# R220J.net
KiCad netlist of a schematic drawn in EAGLE
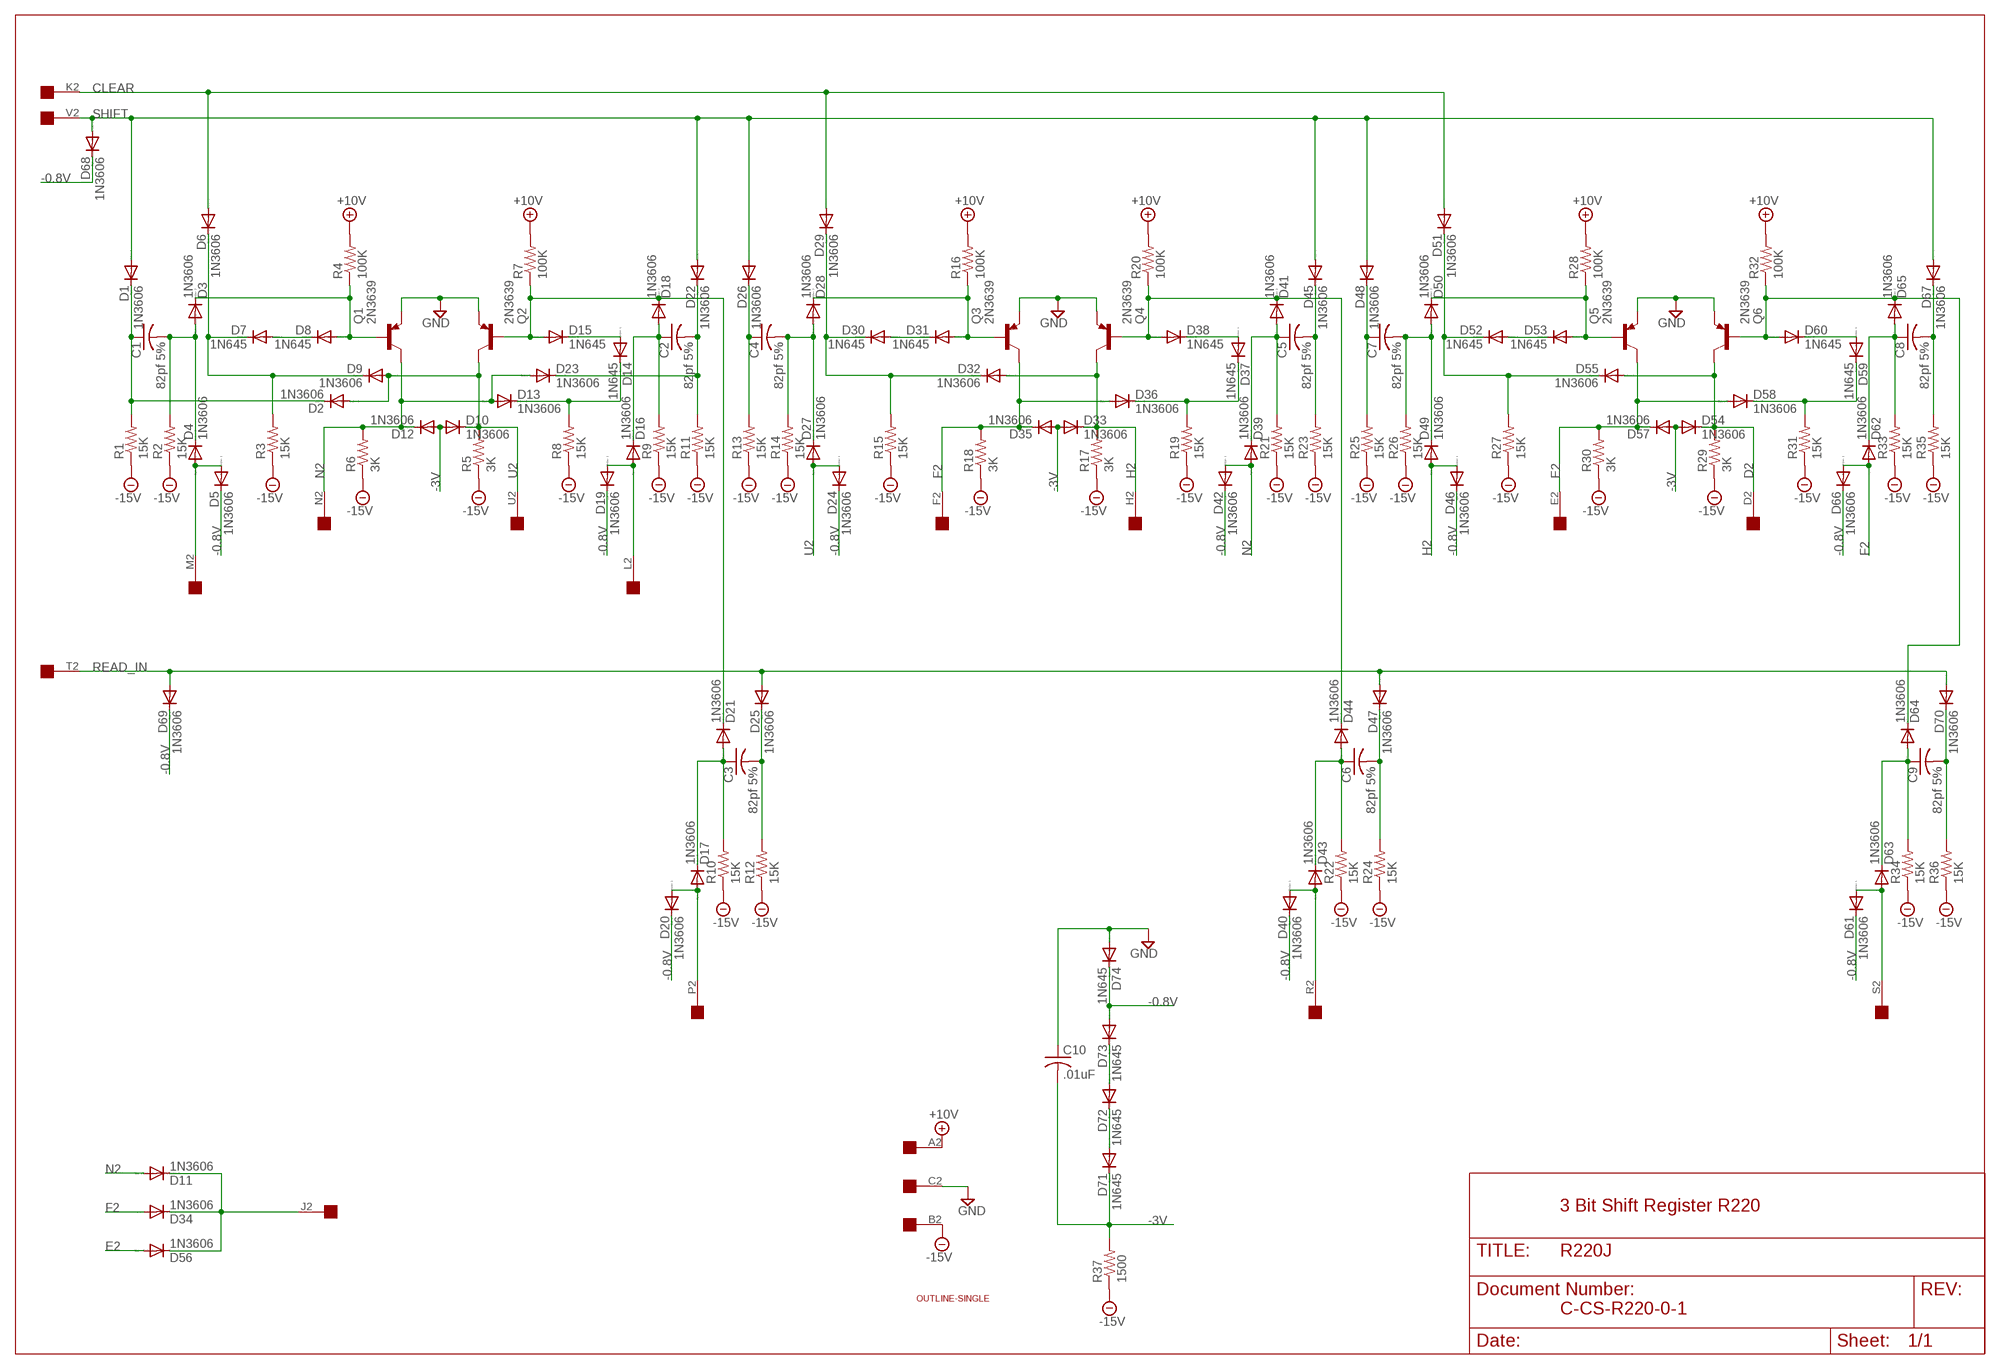
[diagram p0: schematic, sheet 1]

(export (version "E")
  (design (tool "Eeschema 10.0.6"))
  (components
    (comp (ref "C1")
      (value "82pf 5%")
      (footprint "eagle-import:C050-025X075")
      (libsource (lib "eagle-import") (part "C-US050-025X075"))
    )
    (comp (ref "C2")
      (value "82pf 5%")
      (footprint "eagle-import:C050-025X075")
      (libsource (lib "eagle-import") (part "C-US050-025X075"))
    )
    (comp (ref "C3")
      (value "82pf 5%")
      (footprint "eagle-import:C050-025X075")
      (libsource (lib "eagle-import") (part "C-US050-025X075"))
    )
    (comp (ref "C4")
      (value "82pf 5%")
      (footprint "eagle-import:C050-025X075")
      (libsource (lib "eagle-import") (part "C-US050-025X075"))
    )
    (comp (ref "C5")
      (value "82pf 5%")
      (footprint "eagle-import:C050-025X075")
      (libsource (lib "eagle-import") (part "C-US050-025X075"))
    )
    (comp (ref "C6")
      (value "82pf 5%")
      (footprint "eagle-import:C050-025X075")
      (libsource (lib "eagle-import") (part "C-US050-025X075"))
    )
    (comp (ref "C7")
      (value "82pf 5%")
      (footprint "eagle-import:C050-025X075")
      (libsource (lib "eagle-import") (part "C-US050-025X075"))
    )
    (comp (ref "C8")
      (value "82pf 5%")
      (footprint "eagle-import:C050-025X075")
      (libsource (lib "eagle-import") (part "C-US050-025X075"))
    )
    (comp (ref "C9")
      (value "82pf 5%")
      (footprint "eagle-import:C050-025X075")
      (libsource (lib "eagle-import") (part "C-US050-025X075"))
    )
    (comp (ref "C10")
      (value ".01uF")
      (footprint "eagle-import:C050-025X075")
      (libsource (lib "eagle-import") (part "C-US050-025X075"))
    )
    (comp (ref "D1")
      (value "1N3606")
      (footprint "eagle-import:DO35-10")
      (libsource (lib "eagle-import") (part "1N4148DO35-10"))
    )
    (comp (ref "D2")
      (value "1N3606")
      (footprint "eagle-import:DO35-10")
      (libsource (lib "eagle-import") (part "1N4148DO35-10"))
    )
    (comp (ref "D3")
      (value "1N3606")
      (footprint "eagle-import:DO35-10")
      (libsource (lib "eagle-import") (part "1N4148DO35-10"))
    )
    (comp (ref "D4")
      (value "1N3606")
      (footprint "eagle-import:DO35-10")
      (libsource (lib "eagle-import") (part "1N4148DO35-10"))
    )
    (comp (ref "D5")
      (value "1N3606")
      (footprint "eagle-import:DO35-10")
      (libsource (lib "eagle-import") (part "1N4148DO35-10"))
    )
    (comp (ref "D6")
      (value "1N3606")
      (footprint "eagle-import:DO35-10")
      (libsource (lib "eagle-import") (part "1N4148DO35-10"))
    )
    (comp (ref "D7")
      (value "1N645")
      (footprint "eagle-import:DO35-10")
      (libsource (lib "eagle-import") (part "1N4148DO35-10"))
    )
    (comp (ref "D8")
      (value "1N645")
      (footprint "eagle-import:DO35-10")
      (libsource (lib "eagle-import") (part "1N4148DO35-10"))
    )
    (comp (ref "D9")
      (value "1N3606")
      (footprint "eagle-import:DO35-10")
      (libsource (lib "eagle-import") (part "1N4148DO35-10"))
    )
    (comp (ref "D10")
      (value "1N3606")
      (footprint "eagle-import:DO35-10")
      (libsource (lib "eagle-import") (part "1N4148DO35-10"))
    )
    (comp (ref "D11")
      (value "1N3606")
      (footprint "eagle-import:DO35-10")
      (libsource (lib "eagle-import") (part "1N4148DO35-10"))
    )
    (comp (ref "D12")
      (value "1N3606")
      (footprint "eagle-import:DO35-10")
      (libsource (lib "eagle-import") (part "1N4148DO35-10"))
    )
    (comp (ref "D13")
      (value "1N3606")
      (footprint "eagle-import:DO35-10")
      (libsource (lib "eagle-import") (part "1N4148DO35-10"))
    )
    (comp (ref "D14")
      (value "1N645")
      (footprint "eagle-import:DO35-10")
      (libsource (lib "eagle-import") (part "1N4148DO35-10"))
    )
    (comp (ref "D15")
      (value "1N645")
      (footprint "eagle-import:DO35-10")
      (libsource (lib "eagle-import") (part "1N4148DO35-10"))
    )
    (comp (ref "D16")
      (value "1N3606")
      (footprint "eagle-import:DO35-10")
      (libsource (lib "eagle-import") (part "1N4148DO35-10"))
    )
    (comp (ref "D17")
      (value "1N3606")
      (footprint "eagle-import:DO35-10")
      (libsource (lib "eagle-import") (part "1N4148DO35-10"))
    )
    (comp (ref "D18")
      (value "1N3606")
      (footprint "eagle-import:DO35-10")
      (libsource (lib "eagle-import") (part "1N4148DO35-10"))
    )
    (comp (ref "D19")
      (value "1N3606")
      (footprint "eagle-import:DO35-10")
      (libsource (lib "eagle-import") (part "1N4148DO35-10"))
    )
    (comp (ref "D20")
      (value "1N3606")
      (footprint "eagle-import:DO35-10")
      (libsource (lib "eagle-import") (part "1N4148DO35-10"))
    )
    (comp (ref "D21")
      (value "1N3606")
      (footprint "eagle-import:DO35-10")
      (libsource (lib "eagle-import") (part "1N4148DO35-10"))
    )
    (comp (ref "D22")
      (value "1N3606")
      (footprint "eagle-import:DO35-10")
      (libsource (lib "eagle-import") (part "1N4148DO35-10"))
    )
    (comp (ref "D23")
      (value "1N3606")
      (footprint "eagle-import:DO35-10")
      (libsource (lib "eagle-import") (part "1N4148DO35-10"))
    )
    (comp (ref "D24")
      (value "1N3606")
      (footprint "eagle-import:DO35-10")
      (libsource (lib "eagle-import") (part "1N4148DO35-10"))
    )
    (comp (ref "D25")
      (value "1N3606")
      (footprint "eagle-import:DO35-10")
      (libsource (lib "eagle-import") (part "1N4148DO35-10"))
    )
    (comp (ref "D26")
      (value "1N3606")
      (footprint "eagle-import:DO35-10")
      (libsource (lib "eagle-import") (part "1N4148DO35-10"))
    )
    (comp (ref "D27")
      (value "1N3606")
      (footprint "eagle-import:DO35-10")
      (libsource (lib "eagle-import") (part "1N4148DO35-10"))
    )
    (comp (ref "D28")
      (value "1N3606")
      (footprint "eagle-import:DO35-10")
      (libsource (lib "eagle-import") (part "1N4148DO35-10"))
    )
    (comp (ref "D29")
      (value "1N3606")
      (footprint "eagle-import:DO35-10")
      (libsource (lib "eagle-import") (part "1N4148DO35-10"))
    )
    (comp (ref "D30")
      (value "1N645")
      (footprint "eagle-import:DO35-10")
      (libsource (lib "eagle-import") (part "1N4148DO35-10"))
    )
    (comp (ref "D31")
      (value "1N645")
      (footprint "eagle-import:DO35-10")
      (libsource (lib "eagle-import") (part "1N4148DO35-10"))
    )
    (comp (ref "D32")
      (value "1N3606")
      (footprint "eagle-import:DO35-10")
      (libsource (lib "eagle-import") (part "1N4148DO35-10"))
    )
    (comp (ref "D33")
      (value "1N3606")
      (footprint "eagle-import:DO35-10")
      (libsource (lib "eagle-import") (part "1N4148DO35-10"))
    )
    (comp (ref "D34")
      (value "1N3606")
      (footprint "eagle-import:DO35-10")
      (libsource (lib "eagle-import") (part "1N4148DO35-10"))
    )
    (comp (ref "D35")
      (value "1N3606")
      (footprint "eagle-import:DO35-10")
      (libsource (lib "eagle-import") (part "1N4148DO35-10"))
    )
    (comp (ref "D36")
      (value "1N3606")
      (footprint "eagle-import:DO35-10")
      (libsource (lib "eagle-import") (part "1N4148DO35-10"))
    )
    (comp (ref "D37")
      (value "1N645")
      (footprint "eagle-import:DO35-10")
      (libsource (lib "eagle-import") (part "1N4148DO35-10"))
    )
    (comp (ref "D38")
      (value "1N645")
      (footprint "eagle-import:DO35-10")
      (libsource (lib "eagle-import") (part "1N4148DO35-10"))
    )
    (comp (ref "D39")
      (value "1N3606")
      (footprint "eagle-import:DO35-10")
      (libsource (lib "eagle-import") (part "1N4148DO35-10"))
    )
    (comp (ref "D40")
      (value "1N3606")
      (footprint "eagle-import:DO35-10")
      (libsource (lib "eagle-import") (part "1N4148DO35-10"))
    )
    (comp (ref "D41")
      (value "1N3606")
      (footprint "eagle-import:DO35-10")
      (libsource (lib "eagle-import") (part "1N4148DO35-10"))
    )
    (comp (ref "D42")
      (value "1N3606")
      (footprint "eagle-import:DO35-10")
      (libsource (lib "eagle-import") (part "1N4148DO35-10"))
    )
    (comp (ref "D43")
      (value "1N3606")
      (footprint "eagle-import:DO35-10")
      (libsource (lib "eagle-import") (part "1N4148DO35-10"))
    )
    (comp (ref "D44")
      (value "1N3606")
      (footprint "eagle-import:DO35-10")
      (libsource (lib "eagle-import") (part "1N4148DO35-10"))
    )
    (comp (ref "D45")
      (value "1N3606")
      (footprint "eagle-import:DO35-10")
      (libsource (lib "eagle-import") (part "1N4148DO35-10"))
    )
    (comp (ref "D46")
      (value "1N3606")
      (footprint "eagle-import:DO35-10")
      (libsource (lib "eagle-import") (part "1N4148DO35-10"))
    )
    (comp (ref "D47")
      (value "1N3606")
      (footprint "eagle-import:DO35-10")
      (libsource (lib "eagle-import") (part "1N4148DO35-10"))
    )
    (comp (ref "D48")
      (value "1N3606")
      (footprint "eagle-import:DO35-10")
      (libsource (lib "eagle-import") (part "1N4148DO35-10"))
    )
    (comp (ref "D49")
      (value "1N3606")
      (footprint "eagle-import:DO35-10")
      (libsource (lib "eagle-import") (part "1N4148DO35-10"))
    )
    (comp (ref "D50")
      (value "1N3606")
      (footprint "eagle-import:DO35-10")
      (libsource (lib "eagle-import") (part "1N4148DO35-10"))
    )
    (comp (ref "D51")
      (value "1N3606")
      (footprint "eagle-import:DO35-10")
      (libsource (lib "eagle-import") (part "1N4148DO35-10"))
    )
    (comp (ref "D52")
      (value "1N645")
      (footprint "eagle-import:DO35-10")
      (libsource (lib "eagle-import") (part "1N4148DO35-10"))
    )
    (comp (ref "D53")
      (value "1N645")
      (footprint "eagle-import:DO35-10")
      (libsource (lib "eagle-import") (part "1N4148DO35-10"))
    )
    (comp (ref "D54")
      (value "1N3606")
      (footprint "eagle-import:DO35-10")
      (libsource (lib "eagle-import") (part "1N4148DO35-10"))
    )
    (comp (ref "D55")
      (value "1N3606")
      (footprint "eagle-import:DO35-10")
      (libsource (lib "eagle-import") (part "1N4148DO35-10"))
    )
    (comp (ref "D56")
      (value "1N3606")
      (footprint "eagle-import:DO35-10")
      (libsource (lib "eagle-import") (part "1N4148DO35-10"))
    )
    (comp (ref "D57")
      (value "1N3606")
      (footprint "eagle-import:DO35-10")
      (libsource (lib "eagle-import") (part "1N4148DO35-10"))
    )
    (comp (ref "D58")
      (value "1N3606")
      (footprint "eagle-import:DO35-10")
      (libsource (lib "eagle-import") (part "1N4148DO35-10"))
    )
    (comp (ref "D59")
      (value "1N645")
      (footprint "eagle-import:DO35-10")
      (libsource (lib "eagle-import") (part "1N4148DO35-10"))
    )
    (comp (ref "D60")
      (value "1N645")
      (footprint "eagle-import:DO35-10")
      (libsource (lib "eagle-import") (part "1N4148DO35-10"))
    )
    (comp (ref "D61")
      (value "1N3606")
      (footprint "eagle-import:DO35-10")
      (libsource (lib "eagle-import") (part "1N4148DO35-10"))
    )
    (comp (ref "D62")
      (value "1N3606")
      (footprint "eagle-import:DO35-10")
      (libsource (lib "eagle-import") (part "1N4148DO35-10"))
    )
    (comp (ref "D63")
      (value "1N3606")
      (footprint "eagle-import:DO35-10")
      (libsource (lib "eagle-import") (part "1N4148DO35-10"))
    )
    (comp (ref "D64")
      (value "1N3606")
      (footprint "eagle-import:DO35-10")
      (libsource (lib "eagle-import") (part "1N4148DO35-10"))
    )
    (comp (ref "D65")
      (value "1N3606")
      (footprint "eagle-import:DO35-10")
      (libsource (lib "eagle-import") (part "1N4148DO35-10"))
    )
    (comp (ref "D66")
      (value "1N3606")
      (footprint "eagle-import:DO35-10")
      (libsource (lib "eagle-import") (part "1N4148DO35-10"))
    )
    (comp (ref "D67")
      (value "1N3606")
      (footprint "eagle-import:DO35-10")
      (libsource (lib "eagle-import") (part "1N4148DO35-10"))
    )
    (comp (ref "D68")
      (value "1N3606")
      (footprint "eagle-import:DO35-10")
      (libsource (lib "eagle-import") (part "1N4148DO35-10"))
    )
    (comp (ref "D69")
      (value "1N3606")
      (footprint "eagle-import:DO35-10")
      (libsource (lib "eagle-import") (part "1N4148DO35-10"))
    )
    (comp (ref "D70")
      (value "1N3606")
      (footprint "eagle-import:DO35-10")
      (libsource (lib "eagle-import") (part "1N4148DO35-10"))
    )
    (comp (ref "D71")
      (value "1N645")
      (footprint "eagle-import:DO35-10")
      (libsource (lib "eagle-import") (part "1N4148DO35-10"))
    )
    (comp (ref "D72")
      (value "1N645")
      (footprint "eagle-import:DO35-10")
      (libsource (lib "eagle-import") (part "1N4148DO35-10"))
    )
    (comp (ref "D73")
      (value "1N645")
      (footprint "eagle-import:DO35-10")
      (libsource (lib "eagle-import") (part "1N4148DO35-10"))
    )
    (comp (ref "D74")
      (value "1N645")
      (footprint "eagle-import:DO35-10")
      (libsource (lib "eagle-import") (part "1N4148DO35-10"))
    )
    (comp (ref "Q1")
      (value "2N3639")
      (footprint "eagle-import:TO39")
      (libsource (lib "eagle-import") (part "2N3637"))
    )
    (comp (ref "Q2")
      (value "2N3639")
      (footprint "eagle-import:TO39")
      (libsource (lib "eagle-import") (part "2N3637"))
    )
    (comp (ref "Q3")
      (value "2N3639")
      (footprint "eagle-import:TO39")
      (libsource (lib "eagle-import") (part "2N3637"))
    )
    (comp (ref "Q4")
      (value "2N3639")
      (footprint "eagle-import:TO39")
      (libsource (lib "eagle-import") (part "2N3637"))
    )
    (comp (ref "Q5")
      (value "2N3639")
      (footprint "eagle-import:TO39")
      (libsource (lib "eagle-import") (part "2N3637"))
    )
    (comp (ref "Q6")
      (value "2N3639")
      (footprint "eagle-import:TO39")
      (libsource (lib "eagle-import") (part "2N3637"))
    )
    (comp (ref "R1")
      (value "15K")
      (footprint "eagle-import:0207_10")
      (libsource (lib "eagle-import") (part "R-US_0207/10"))
    )
    (comp (ref "R2")
      (value "15K")
      (footprint "eagle-import:0207_10")
      (libsource (lib "eagle-import") (part "R-US_0207/10"))
    )
    (comp (ref "R3")
      (value "15K")
      (footprint "eagle-import:0207_10")
      (libsource (lib "eagle-import") (part "R-US_0207/10"))
    )
    (comp (ref "R4")
      (value "100K")
      (footprint "eagle-import:0207_10")
      (libsource (lib "eagle-import") (part "R-US_0207/10"))
    )
    (comp (ref "R5")
      (value "3K")
      (footprint "eagle-import:0207_10")
      (libsource (lib "eagle-import") (part "R-US_0207/10"))
    )
    (comp (ref "R6")
      (value "3K")
      (footprint "eagle-import:0207_10")
      (libsource (lib "eagle-import") (part "R-US_0207/10"))
    )
    (comp (ref "R7")
      (value "100K")
      (footprint "eagle-import:0207_10")
      (libsource (lib "eagle-import") (part "R-US_0207/10"))
    )
    (comp (ref "R8")
      (value "15K")
      (footprint "eagle-import:0207_10")
      (libsource (lib "eagle-import") (part "R-US_0207/10"))
    )
    (comp (ref "R9")
      (value "15K")
      (footprint "eagle-import:0207_10")
      (libsource (lib "eagle-import") (part "R-US_0207/10"))
    )
    (comp (ref "R10")
      (value "15K")
      (footprint "eagle-import:0207_10")
      (libsource (lib "eagle-import") (part "R-US_0207/10"))
    )
    (comp (ref "R11")
      (value "15K")
      (footprint "eagle-import:0207_10")
      (libsource (lib "eagle-import") (part "R-US_0207/10"))
    )
    (comp (ref "R12")
      (value "15K")
      (footprint "eagle-import:0207_10")
      (libsource (lib "eagle-import") (part "R-US_0207/10"))
    )
    (comp (ref "R13")
      (value "15K")
      (footprint "eagle-import:0207_10")
      (libsource (lib "eagle-import") (part "R-US_0207/10"))
    )
    (comp (ref "R14")
      (value "15K")
      (footprint "eagle-import:0207_10")
      (libsource (lib "eagle-import") (part "R-US_0207/10"))
    )
    (comp (ref "R15")
      (value "15K")
      (footprint "eagle-import:0207_10")
      (libsource (lib "eagle-import") (part "R-US_0207/10"))
    )
    (comp (ref "R16")
      (value "100K")
      (footprint "eagle-import:0207_10")
      (libsource (lib "eagle-import") (part "R-US_0207/10"))
    )
    (comp (ref "R17")
      (value "3K")
      (footprint "eagle-import:0207_10")
      (libsource (lib "eagle-import") (part "R-US_0207/10"))
    )
    (comp (ref "R18")
      (value "3K")
      (footprint "eagle-import:0207_10")
      (libsource (lib "eagle-import") (part "R-US_0207/10"))
    )
    (comp (ref "R19")
      (value "15K")
      (footprint "eagle-import:0207_10")
      (libsource (lib "eagle-import") (part "R-US_0207/10"))
    )
    (comp (ref "R20")
      (value "100K")
      (footprint "eagle-import:0207_10")
      (libsource (lib "eagle-import") (part "R-US_0207/10"))
    )
    (comp (ref "R21")
      (value "15K")
      (footprint "eagle-import:0207_10")
      (libsource (lib "eagle-import") (part "R-US_0207/10"))
    )
    (comp (ref "R22")
      (value "15K")
      (footprint "eagle-import:0207_10")
      (libsource (lib "eagle-import") (part "R-US_0207/10"))
    )
    (comp (ref "R23")
      (value "15K")
      (footprint "eagle-import:0207_10")
      (libsource (lib "eagle-import") (part "R-US_0207/10"))
    )
    (comp (ref "R24")
      (value "15K")
      (footprint "eagle-import:0207_10")
      (libsource (lib "eagle-import") (part "R-US_0207/10"))
    )
    (comp (ref "R25")
      (value "15K")
      (footprint "eagle-import:0207_10")
      (libsource (lib "eagle-import") (part "R-US_0207/10"))
    )
    (comp (ref "R26")
      (value "15K")
      (footprint "eagle-import:0207_10")
      (libsource (lib "eagle-import") (part "R-US_0207/10"))
    )
    (comp (ref "R27")
      (value "15K")
      (footprint "eagle-import:0207_10")
      (libsource (lib "eagle-import") (part "R-US_0207/10"))
    )
    (comp (ref "R28")
      (value "100K")
      (footprint "eagle-import:0207_10")
      (libsource (lib "eagle-import") (part "R-US_0207/10"))
    )
    (comp (ref "R29")
      (value "3K")
      (footprint "eagle-import:0207_10")
      (libsource (lib "eagle-import") (part "R-US_0207/10"))
    )
    (comp (ref "R30")
      (value "3K")
      (footprint "eagle-import:0207_10")
      (libsource (lib "eagle-import") (part "R-US_0207/10"))
    )
    (comp (ref "R31")
      (value "15K")
      (footprint "eagle-import:0207_10")
      (libsource (lib "eagle-import") (part "R-US_0207/10"))
    )
    (comp (ref "R32")
      (value "100K")
      (footprint "eagle-import:0207_10")
      (libsource (lib "eagle-import") (part "R-US_0207/10"))
    )
    (comp (ref "R33")
      (value "15K")
      (footprint "eagle-import:0207_10")
      (libsource (lib "eagle-import") (part "R-US_0207/10"))
    )
    (comp (ref "R34")
      (value "15K")
      (footprint "eagle-import:0207_10")
      (libsource (lib "eagle-import") (part "R-US_0207/10"))
    )
    (comp (ref "R35")
      (value "15K")
      (footprint "eagle-import:0207_10")
      (libsource (lib "eagle-import") (part "R-US_0207/10"))
    )
    (comp (ref "R36")
      (value "15K")
      (footprint "eagle-import:0207_10")
      (libsource (lib "eagle-import") (part "R-US_0207/10"))
    )
    (comp (ref "R37")
      (value "1500")
      (footprint "eagle-import:0207_10")
      (libsource (lib "eagle-import") (part "R-US_0207/10"))
    )
    (comp (ref "U$1")
      (value "OUTLINE-SINGLE")
      (footprint "eagle-import:SINGLE")
      (libsource (lib "eagle-import") (part "OUTLINE-SINGLE"))
    )
    (comp (ref "U$2")
      (value "EDGE-1")
      (footprint "eagle-import:EDGE-CON1")
      (libsource (lib "eagle-import") (part "EDGE-1"))
    )
  )
  (nets
    (net (code "1") (name "+10V") (class "Default")
      (node (ref "R16") (pin "2") (pinfunction "2_2") (pintype "passive"))
      (node (ref "R20") (pin "2") (pinfunction "2_2") (pintype "passive"))
      (node (ref "R28") (pin "2") (pinfunction "2_2") (pintype "passive"))
      (node (ref "R32") (pin "2") (pinfunction "2_2") (pintype "passive"))
      (node (ref "R4") (pin "2") (pinfunction "2_2") (pintype "passive"))
      (node (ref "R7") (pin "2") (pinfunction "2_2") (pintype "passive"))
      (node (ref "U$2") (pin "A2") (pinfunction "1_A2") (pintype "bidirectional"))
    )
    (net (code "2") (name "-15V") (class "Default")
      (node (ref "R1") (pin "1") (pinfunction "1_1") (pintype "passive"))
      (node (ref "R10") (pin "1") (pinfunction "1_1") (pintype "passive"))
      (node (ref "R11") (pin "1") (pinfunction "1_1") (pintype "passive"))
      (node (ref "R12") (pin "1") (pinfunction "1_1") (pintype "passive"))
      (node (ref "R13") (pin "1") (pinfunction "1_1") (pintype "passive"))
      (node (ref "R14") (pin "1") (pinfunction "1_1") (pintype "passive"))
      (node (ref "R15") (pin "1") (pinfunction "1_1") (pintype "passive"))
      (node (ref "R17") (pin "1") (pinfunction "1_1") (pintype "passive"))
      (node (ref "R18") (pin "1") (pinfunction "1_1") (pintype "passive"))
      (node (ref "R19") (pin "1") (pinfunction "1_1") (pintype "passive"))
      (node (ref "R2") (pin "1") (pinfunction "1_1") (pintype "passive"))
      (node (ref "R21") (pin "1") (pinfunction "1_1") (pintype "passive"))
      (node (ref "R22") (pin "1") (pinfunction "1_1") (pintype "passive"))
      (node (ref "R23") (pin "1") (pinfunction "1_1") (pintype "passive"))
      (node (ref "R24") (pin "1") (pinfunction "1_1") (pintype "passive"))
      (node (ref "R25") (pin "1") (pinfunction "1_1") (pintype "passive"))
      (node (ref "R26") (pin "1") (pinfunction "1_1") (pintype "passive"))
      (node (ref "R27") (pin "1") (pinfunction "1_1") (pintype "passive"))
      (node (ref "R29") (pin "1") (pinfunction "1_1") (pintype "passive"))
      (node (ref "R3") (pin "1") (pinfunction "1_1") (pintype "passive"))
      (node (ref "R30") (pin "1") (pinfunction "1_1") (pintype "passive"))
      (node (ref "R31") (pin "1") (pinfunction "1_1") (pintype "passive"))
      (node (ref "R33") (pin "1") (pinfunction "1_1") (pintype "passive"))
      (node (ref "R34") (pin "1") (pinfunction "1_1") (pintype "passive"))
      (node (ref "R35") (pin "1") (pinfunction "1_1") (pintype "passive"))
      (node (ref "R36") (pin "1") (pinfunction "1_1") (pintype "passive"))
      (node (ref "R37") (pin "1") (pinfunction "1_1") (pintype "passive"))
      (node (ref "R5") (pin "1") (pinfunction "1_1") (pintype "passive"))
      (node (ref "R6") (pin "1") (pinfunction "1_1") (pintype "passive"))
      (node (ref "R8") (pin "1") (pinfunction "1_1") (pintype "passive"))
      (node (ref "R9") (pin "1") (pinfunction "1_1") (pintype "passive"))
      (node (ref "U$2") (pin "B2") (pinfunction "1_B2") (pintype "bidirectional"))
    )
    (net (code "3") (name "/-0.8V") (class "Default")
      (node (ref "D19") (pin "C") (pinfunction "C_C") (pintype "passive"))
      (node (ref "D20") (pin "C") (pinfunction "C_C") (pintype "passive"))
      (node (ref "D24") (pin "C") (pinfunction "C_C") (pintype "passive"))
      (node (ref "D40") (pin "C") (pinfunction "C_C") (pintype "passive"))
      (node (ref "D42") (pin "C") (pinfunction "C_C") (pintype "passive"))
      (node (ref "D46") (pin "C") (pinfunction "C_C") (pintype "passive"))
      (node (ref "D5") (pin "C") (pinfunction "C_C") (pintype "passive"))
      (node (ref "D61") (pin "C") (pinfunction "C_C") (pintype "passive"))
      (node (ref "D66") (pin "C") (pinfunction "C_C") (pintype "passive"))
      (node (ref "D68") (pin "C") (pinfunction "C_C") (pintype "passive"))
      (node (ref "D69") (pin "C") (pinfunction "C_C") (pintype "passive"))
      (node (ref "D73") (pin "A") (pinfunction "A_A") (pintype "passive"))
      (node (ref "D74") (pin "C") (pinfunction "C_C") (pintype "passive"))
    )
    (net (code "4") (name "/-3V") (class "Default")
      (node (ref "C10") (pin "2") (pinfunction "2_2") (pintype "passive"))
      (node (ref "D10") (pin "A") (pinfunction "A_A") (pintype "passive"))
      (node (ref "D12") (pin "A") (pinfunction "A_A") (pintype "passive"))
      (node (ref "D33") (pin "A") (pinfunction "A_A") (pintype "passive"))
      (node (ref "D35") (pin "A") (pinfunction "A_A") (pintype "passive"))
      (node (ref "D54") (pin "A") (pinfunction "A_A") (pintype "passive"))
      (node (ref "D57") (pin "A") (pinfunction "A_A") (pintype "passive"))
      (node (ref "D71") (pin "C") (pinfunction "C_C") (pintype "passive"))
      (node (ref "R37") (pin "2") (pinfunction "2_2") (pintype "passive"))
    )
    (net (code "5") (name "/CLEAR") (class "Default")
      (node (ref "D29") (pin "A") (pinfunction "A_A") (pintype "passive"))
      (node (ref "D51") (pin "A") (pinfunction "A_A") (pintype "passive"))
      (node (ref "D6") (pin "A") (pinfunction "A_A") (pintype "passive"))
      (node (ref "U$2") (pin "K2") (pinfunction "1_K2") (pintype "bidirectional"))
    )
    (net (code "6") (name "/D2") (class "Default")
      (node (ref "D54") (pin "C") (pinfunction "C_C") (pintype "passive"))
      (node (ref "D55") (pin "A") (pinfunction "A_A") (pintype "passive"))
      (node (ref "Q6") (pin "3") (pinfunction "C_3") (pintype "passive"))
      (node (ref "R29") (pin "2") (pinfunction "2_2") (pintype "passive"))
      (node (ref "U$2") (pin "D2") (pinfunction "1_D2") (pintype "bidirectional"))
    )
    (net (code "7") (name "/E2") (class "Default")
      (node (ref "D56") (pin "A") (pinfunction "A_A") (pintype "passive"))
      (node (ref "D57") (pin "C") (pinfunction "C_C") (pintype "passive"))
      (node (ref "D58") (pin "A") (pinfunction "A_A") (pintype "passive"))
      (node (ref "Q5") (pin "3") (pinfunction "C_3") (pintype "passive"))
      (node (ref "R30") (pin "2") (pinfunction "2_2") (pintype "passive"))
      (node (ref "U$2") (pin "E2") (pinfunction "1_E2") (pintype "bidirectional"))
    )
    (net (code "8") (name "/F2") (class "Default")
      (node (ref "D34") (pin "A") (pinfunction "A_A") (pintype "passive"))
      (node (ref "D35") (pin "C") (pinfunction "C_C") (pintype "passive"))
      (node (ref "D36") (pin "A") (pinfunction "A_A") (pintype "passive"))
      (node (ref "D62") (pin "A") (pinfunction "A_A") (pintype "passive"))
      (node (ref "D66") (pin "A") (pinfunction "A_A") (pintype "passive"))
      (node (ref "Q3") (pin "3") (pinfunction "C_3") (pintype "passive"))
      (node (ref "R18") (pin "2") (pinfunction "2_2") (pintype "passive"))
      (node (ref "U$2") (pin "F2") (pinfunction "1_F2") (pintype "bidirectional"))
    )
    (net (code "9") (name "/H2") (class "Default")
      (node (ref "D32") (pin "A") (pinfunction "A_A") (pintype "passive"))
      (node (ref "D33") (pin "C") (pinfunction "C_C") (pintype "passive"))
      (node (ref "D46") (pin "A") (pinfunction "A_A") (pintype "passive"))
      (node (ref "D49") (pin "A") (pinfunction "A_A") (pintype "passive"))
      (node (ref "Q4") (pin "3") (pinfunction "C_3") (pintype "passive"))
      (node (ref "R17") (pin "2") (pinfunction "2_2") (pintype "passive"))
      (node (ref "U$2") (pin "H2") (pinfunction "1_H2") (pintype "bidirectional"))
    )
    (net (code "10") (name "/N2") (class "Default")
      (node (ref "D11") (pin "A") (pinfunction "A_A") (pintype "passive"))
      (node (ref "D12") (pin "C") (pinfunction "C_C") (pintype "passive"))
      (node (ref "D13") (pin "A") (pinfunction "A_A") (pintype "passive"))
      (node (ref "D23") (pin "A") (pinfunction "A_A") (pintype "passive"))
      (node (ref "D39") (pin "A") (pinfunction "A_A") (pintype "passive"))
      (node (ref "D42") (pin "A") (pinfunction "A_A") (pintype "passive"))
      (node (ref "Q1") (pin "3") (pinfunction "C_3") (pintype "passive"))
      (node (ref "R6") (pin "2") (pinfunction "2_2") (pintype "passive"))
      (node (ref "U$2") (pin "N2") (pinfunction "1_N2") (pintype "bidirectional"))
    )
    (net (code "11") (name "/READ_IN") (class "Default")
      (node (ref "D25") (pin "A") (pinfunction "A_A") (pintype "passive"))
      (node (ref "D47") (pin "A") (pinfunction "A_A") (pintype "passive"))
      (node (ref "D69") (pin "A") (pinfunction "A_A") (pintype "passive"))
      (node (ref "D70") (pin "A") (pinfunction "A_A") (pintype "passive"))
      (node (ref "U$2") (pin "T2") (pinfunction "1_T2") (pintype "bidirectional"))
    )
    (net (code "12") (name "/SHIFT") (class "Default")
      (node (ref "D1") (pin "A") (pinfunction "A_A") (pintype "passive"))
      (node (ref "D22") (pin "A") (pinfunction "A_A") (pintype "passive"))
      (node (ref "D26") (pin "A") (pinfunction "A_A") (pintype "passive"))
      (node (ref "D45") (pin "A") (pinfunction "A_A") (pintype "passive"))
      (node (ref "D48") (pin "A") (pinfunction "A_A") (pintype "passive"))
      (node (ref "D67") (pin "A") (pinfunction "A_A") (pintype "passive"))
      (node (ref "D68") (pin "A") (pinfunction "A_A") (pintype "passive"))
      (node (ref "U$2") (pin "V2") (pinfunction "1_V2") (pintype "bidirectional"))
    )
    (net (code "13") (name "/U2") (class "Default")
      (node (ref "D10") (pin "C") (pinfunction "C_C") (pintype "passive"))
      (node (ref "D2") (pin "A") (pinfunction "A_A") (pintype "passive"))
      (node (ref "D24") (pin "A") (pinfunction "A_A") (pintype "passive"))
      (node (ref "D27") (pin "A") (pinfunction "A_A") (pintype "passive"))
      (node (ref "D9") (pin "A") (pinfunction "A_A") (pintype "passive"))
      (node (ref "Q2") (pin "3") (pinfunction "C_3") (pintype "passive"))
      (node (ref "R5") (pin "2") (pinfunction "2_2") (pintype "passive"))
      (node (ref "U$2") (pin "U2") (pinfunction "1_U2") (pintype "bidirectional"))
    )
    (net (code "14") (name "GND") (class "Default")
      (node (ref "C10") (pin "1") (pinfunction "1_1") (pintype "passive"))
      (node (ref "D74") (pin "A") (pinfunction "A_A") (pintype "passive"))
      (node (ref "Q1") (pin "1") (pinfunction "E_1") (pintype "passive"))
      (node (ref "Q2") (pin "1") (pinfunction "E_1") (pintype "passive"))
      (node (ref "Q3") (pin "1") (pinfunction "E_1") (pintype "passive"))
      (node (ref "Q4") (pin "1") (pinfunction "E_1") (pintype "passive"))
      (node (ref "Q5") (pin "1") (pinfunction "E_1") (pintype "passive"))
      (node (ref "Q6") (pin "1") (pinfunction "E_1") (pintype "passive"))
      (node (ref "U$2") (pin "C2") (pinfunction "1_C2") (pintype "bidirectional"))
    )
    (net (code "15") (name "Net-(C1-Pad1)") (class "Default")
      (node (ref "C1") (pin "1") (pinfunction "1_1") (pintype "passive"))
      (node (ref "D1") (pin "C") (pinfunction "C_C") (pintype "passive"))
      (node (ref "D2") (pin "C") (pinfunction "C_C") (pintype "passive"))
      (node (ref "R1") (pin "2") (pinfunction "2_2") (pintype "passive"))
    )
    (net (code "16") (name "Net-(C1-Pad2)") (class "Default")
      (node (ref "C1") (pin "2") (pinfunction "2_2") (pintype "passive"))
      (node (ref "D3") (pin "A") (pinfunction "A_A") (pintype "passive"))
      (node (ref "D4") (pin "C") (pinfunction "C_C") (pintype "passive"))
      (node (ref "R2") (pin "2") (pinfunction "2_2") (pintype "passive"))
    )
    (net (code "17") (name "Net-(C2-Pad1)") (class "Default")
      (node (ref "C2") (pin "1") (pinfunction "1_1") (pintype "passive"))
      (node (ref "D16") (pin "C") (pinfunction "C_C") (pintype "passive"))
      (node (ref "D18") (pin "A") (pinfunction "A_A") (pintype "passive"))
      (node (ref "R9") (pin "2") (pinfunction "2_2") (pintype "passive"))
    )
    (net (code "18") (name "Net-(C2-Pad2)") (class "Default")
      (node (ref "C2") (pin "2") (pinfunction "2_2") (pintype "passive"))
      (node (ref "D22") (pin "C") (pinfunction "C_C") (pintype "passive"))
      (node (ref "D23") (pin "C") (pinfunction "C_C") (pintype "passive"))
      (node (ref "R11") (pin "2") (pinfunction "2_2") (pintype "passive"))
    )
    (net (code "19") (name "Net-(C3-Pad1)") (class "Default")
      (node (ref "C3") (pin "1") (pinfunction "1_1") (pintype "passive"))
      (node (ref "D17") (pin "C") (pinfunction "C_C") (pintype "passive"))
      (node (ref "D21") (pin "A") (pinfunction "A_A") (pintype "passive"))
      (node (ref "R10") (pin "2") (pinfunction "2_2") (pintype "passive"))
    )
    (net (code "20") (name "Net-(C3-Pad2)") (class "Default")
      (node (ref "C3") (pin "2") (pinfunction "2_2") (pintype "passive"))
      (node (ref "D25") (pin "C") (pinfunction "C_C") (pintype "passive"))
      (node (ref "R12") (pin "2") (pinfunction "2_2") (pintype "passive"))
    )
    (net (code "21") (name "Net-(C4-Pad1)") (class "Default")
      (node (ref "C4") (pin "1") (pinfunction "1_1") (pintype "passive"))
      (node (ref "D26") (pin "C") (pinfunction "C_C") (pintype "passive"))
      (node (ref "R13") (pin "2") (pinfunction "2_2") (pintype "passive"))
    )
    (net (code "22") (name "Net-(C4-Pad2)") (class "Default")
      (node (ref "C4") (pin "2") (pinfunction "2_2") (pintype "passive"))
      (node (ref "D27") (pin "C") (pinfunction "C_C") (pintype "passive"))
      (node (ref "D28") (pin "A") (pinfunction "A_A") (pintype "passive"))
      (node (ref "R14") (pin "2") (pinfunction "2_2") (pintype "passive"))
    )
    (net (code "23") (name "Net-(C5-Pad1)") (class "Default")
      (node (ref "C5") (pin "1") (pinfunction "1_1") (pintype "passive"))
      (node (ref "D39") (pin "C") (pinfunction "C_C") (pintype "passive"))
      (node (ref "D41") (pin "A") (pinfunction "A_A") (pintype "passive"))
      (node (ref "R21") (pin "2") (pinfunction "2_2") (pintype "passive"))
    )
    (net (code "24") (name "Net-(C5-Pad2)") (class "Default")
      (node (ref "C5") (pin "2") (pinfunction "2_2") (pintype "passive"))
      (node (ref "D45") (pin "C") (pinfunction "C_C") (pintype "passive"))
      (node (ref "R23") (pin "2") (pinfunction "2_2") (pintype "passive"))
    )
    (net (code "25") (name "Net-(C6-Pad1)") (class "Default")
      (node (ref "C6") (pin "1") (pinfunction "1_1") (pintype "passive"))
      (node (ref "D43") (pin "C") (pinfunction "C_C") (pintype "passive"))
      (node (ref "D44") (pin "A") (pinfunction "A_A") (pintype "passive"))
      (node (ref "R22") (pin "2") (pinfunction "2_2") (pintype "passive"))
    )
    (net (code "26") (name "Net-(C6-Pad2)") (class "Default")
      (node (ref "C6") (pin "2") (pinfunction "2_2") (pintype "passive"))
      (node (ref "D47") (pin "C") (pinfunction "C_C") (pintype "passive"))
      (node (ref "R24") (pin "2") (pinfunction "2_2") (pintype "passive"))
    )
    (net (code "27") (name "Net-(C7-Pad1)") (class "Default")
      (node (ref "C7") (pin "1") (pinfunction "1_1") (pintype "passive"))
      (node (ref "D48") (pin "C") (pinfunction "C_C") (pintype "passive"))
      (node (ref "R25") (pin "2") (pinfunction "2_2") (pintype "passive"))
    )
    (net (code "28") (name "Net-(C7-Pad2)") (class "Default")
      (node (ref "C7") (pin "2") (pinfunction "2_2") (pintype "passive"))
      (node (ref "D49") (pin "C") (pinfunction "C_C") (pintype "passive"))
      (node (ref "D50") (pin "A") (pinfunction "A_A") (pintype "passive"))
      (node (ref "R26") (pin "2") (pinfunction "2_2") (pintype "passive"))
    )
    (net (code "29") (name "Net-(C8-Pad1)") (class "Default")
      (node (ref "C8") (pin "1") (pinfunction "1_1") (pintype "passive"))
      (node (ref "D62") (pin "C") (pinfunction "C_C") (pintype "passive"))
      (node (ref "D65") (pin "A") (pinfunction "A_A") (pintype "passive"))
      (node (ref "R33") (pin "2") (pinfunction "2_2") (pintype "passive"))
    )
    (net (code "30") (name "Net-(C8-Pad2)") (class "Default")
      (node (ref "C8") (pin "2") (pinfunction "2_2") (pintype "passive"))
      (node (ref "D67") (pin "C") (pinfunction "C_C") (pintype "passive"))
      (node (ref "R35") (pin "2") (pinfunction "2_2") (pintype "passive"))
    )
    (net (code "31") (name "Net-(C9-Pad1)") (class "Default")
      (node (ref "C9") (pin "1") (pinfunction "1_1") (pintype "passive"))
      (node (ref "D63") (pin "C") (pinfunction "C_C") (pintype "passive"))
      (node (ref "D64") (pin "A") (pinfunction "A_A") (pintype "passive"))
      (node (ref "R34") (pin "2") (pinfunction "2_2") (pintype "passive"))
    )
    (net (code "32") (name "Net-(C9-Pad2)") (class "Default")
      (node (ref "C9") (pin "2") (pinfunction "2_2") (pintype "passive"))
      (node (ref "D70") (pin "C") (pinfunction "C_C") (pintype "passive"))
      (node (ref "R36") (pin "2") (pinfunction "2_2") (pintype "passive"))
    )
    (net (code "33") (name "Net-(D6-PadC)") (class "Default")
      (node (ref "D6") (pin "C") (pinfunction "C_C") (pintype "passive"))
      (node (ref "D7") (pin "C") (pinfunction "C_C") (pintype "passive"))
      (node (ref "D9") (pin "C") (pinfunction "C_C") (pintype "passive"))
      (node (ref "R3") (pin "2") (pinfunction "2_2") (pintype "passive"))
    )
    (net (code "34") (name "Net-(D7-PadA)") (class "Default")
      (node (ref "D7") (pin "A") (pinfunction "A_A") (pintype "passive"))
      (node (ref "D8") (pin "C") (pinfunction "C_C") (pintype "passive"))
    )
    (net (code "35") (name "Net-(D13-PadC)") (class "Default")
      (node (ref "D13") (pin "C") (pinfunction "C_C") (pintype "passive"))
      (node (ref "D14") (pin "C") (pinfunction "C_C") (pintype "passive"))
      (node (ref "R8") (pin "2") (pinfunction "2_2") (pintype "passive"))
    )
    (net (code "36") (name "Net-(D14-PadA)") (class "Default")
      (node (ref "D14") (pin "A") (pinfunction "A_A") (pintype "passive"))
      (node (ref "D15") (pin "C") (pinfunction "C_C") (pintype "passive"))
    )
    (net (code "37") (name "Net-(D29-PadC)") (class "Default")
      (node (ref "D29") (pin "C") (pinfunction "C_C") (pintype "passive"))
      (node (ref "D30") (pin "C") (pinfunction "C_C") (pintype "passive"))
      (node (ref "D32") (pin "C") (pinfunction "C_C") (pintype "passive"))
      (node (ref "R15") (pin "2") (pinfunction "2_2") (pintype "passive"))
    )
    (net (code "38") (name "Net-(D30-PadA)") (class "Default")
      (node (ref "D30") (pin "A") (pinfunction "A_A") (pintype "passive"))
      (node (ref "D31") (pin "C") (pinfunction "C_C") (pintype "passive"))
    )
    (net (code "39") (name "Net-(D36-PadC)") (class "Default")
      (node (ref "D36") (pin "C") (pinfunction "C_C") (pintype "passive"))
      (node (ref "D37") (pin "C") (pinfunction "C_C") (pintype "passive"))
      (node (ref "R19") (pin "2") (pinfunction "2_2") (pintype "passive"))
    )
    (net (code "40") (name "Net-(D37-PadA)") (class "Default")
      (node (ref "D37") (pin "A") (pinfunction "A_A") (pintype "passive"))
      (node (ref "D38") (pin "C") (pinfunction "C_C") (pintype "passive"))
    )
    (net (code "41") (name "Net-(D51-PadC)") (class "Default")
      (node (ref "D51") (pin "C") (pinfunction "C_C") (pintype "passive"))
      (node (ref "D52") (pin "C") (pinfunction "C_C") (pintype "passive"))
      (node (ref "D55") (pin "C") (pinfunction "C_C") (pintype "passive"))
      (node (ref "R27") (pin "2") (pinfunction "2_2") (pintype "passive"))
    )
    (net (code "42") (name "Net-(D52-PadA)") (class "Default")
      (node (ref "D52") (pin "A") (pinfunction "A_A") (pintype "passive"))
      (node (ref "D53") (pin "C") (pinfunction "C_C") (pintype "passive"))
    )
    (net (code "43") (name "Net-(D58-PadC)") (class "Default")
      (node (ref "D58") (pin "C") (pinfunction "C_C") (pintype "passive"))
      (node (ref "D59") (pin "C") (pinfunction "C_C") (pintype "passive"))
      (node (ref "R31") (pin "2") (pinfunction "2_2") (pintype "passive"))
    )
    (net (code "44") (name "Net-(D59-PadA)") (class "Default")
      (node (ref "D59") (pin "A") (pinfunction "A_A") (pintype "passive"))
      (node (ref "D60") (pin "C") (pinfunction "C_C") (pintype "passive"))
    )
    (net (code "45") (name "Net-(D71-PadA)") (class "Default")
      (node (ref "D71") (pin "A") (pinfunction "A_A") (pintype "passive"))
      (node (ref "D72") (pin "C") (pinfunction "C_C") (pintype "passive"))
    )
    (net (code "46") (name "Net-(D72-PadA)") (class "Default")
      (node (ref "D72") (pin "A") (pinfunction "A_A") (pintype "passive"))
      (node (ref "D73") (pin "C") (pinfunction "C_C") (pintype "passive"))
    )
    (net (code "47") (name "Net-(Q1-B)") (class "Default")
      (node (ref "D3") (pin "C") (pinfunction "C_C") (pintype "passive"))
      (node (ref "D8") (pin "A") (pinfunction "A_A") (pintype "passive"))
      (node (ref "Q1") (pin "2") (pinfunction "B_2") (pintype "passive"))
      (node (ref "R4") (pin "1") (pinfunction "1_1") (pintype "passive"))
    )
    (net (code "48") (name "Net-(Q2-B)") (class "Default")
      (node (ref "D15") (pin "A") (pinfunction "A_A") (pintype "passive"))
      (node (ref "D18") (pin "C") (pinfunction "C_C") (pintype "passive"))
      (node (ref "D21") (pin "C") (pinfunction "C_C") (pintype "passive"))
      (node (ref "Q2") (pin "2") (pinfunction "B_2") (pintype "passive"))
      (node (ref "R7") (pin "1") (pinfunction "1_1") (pintype "passive"))
    )
    (net (code "49") (name "Net-(Q3-B)") (class "Default")
      (node (ref "D28") (pin "C") (pinfunction "C_C") (pintype "passive"))
      (node (ref "D31") (pin "A") (pinfunction "A_A") (pintype "passive"))
      (node (ref "Q3") (pin "2") (pinfunction "B_2") (pintype "passive"))
      (node (ref "R16") (pin "1") (pinfunction "1_1") (pintype "passive"))
    )
    (net (code "50") (name "Net-(Q4-B)") (class "Default")
      (node (ref "D38") (pin "A") (pinfunction "A_A") (pintype "passive"))
      (node (ref "D41") (pin "C") (pinfunction "C_C") (pintype "passive"))
      (node (ref "D44") (pin "C") (pinfunction "C_C") (pintype "passive"))
      (node (ref "Q4") (pin "2") (pinfunction "B_2") (pintype "passive"))
      (node (ref "R20") (pin "1") (pinfunction "1_1") (pintype "passive"))
    )
    (net (code "51") (name "Net-(Q5-B)") (class "Default")
      (node (ref "D50") (pin "C") (pinfunction "C_C") (pintype "passive"))
      (node (ref "D53") (pin "A") (pinfunction "A_A") (pintype "passive"))
      (node (ref "Q5") (pin "2") (pinfunction "B_2") (pintype "passive"))
      (node (ref "R28") (pin "1") (pinfunction "1_1") (pintype "passive"))
    )
    (net (code "52") (name "Net-(Q6-B)") (class "Default")
      (node (ref "D60") (pin "A") (pinfunction "A_A") (pintype "passive"))
      (node (ref "D64") (pin "C") (pinfunction "C_C") (pintype "passive"))
      (node (ref "D65") (pin "C") (pinfunction "C_C") (pintype "passive"))
      (node (ref "Q6") (pin "2") (pinfunction "B_2") (pintype "passive"))
      (node (ref "R32") (pin "1") (pinfunction "1_1") (pintype "passive"))
    )
    (net (code "53") (name "Net-(U$2H-1)") (class "Default")
      (node (ref "D11") (pin "C") (pinfunction "C_C") (pintype "passive"))
      (node (ref "D34") (pin "C") (pinfunction "C_C") (pintype "passive"))
      (node (ref "D56") (pin "C") (pinfunction "C_C") (pintype "passive"))
      (node (ref "U$2") (pin "J2") (pinfunction "1_J2") (pintype "bidirectional"))
    )
    (net (code "54") (name "Net-(U$2J-1)") (class "Default")
      (node (ref "D16") (pin "A") (pinfunction "A_A") (pintype "passive"))
      (node (ref "D19") (pin "A") (pinfunction "A_A") (pintype "passive"))
      (node (ref "U$2") (pin "L2") (pinfunction "1_L2") (pintype "bidirectional"))
    )
    (net (code "55") (name "Net-(U$2K-1)") (class "Default")
      (node (ref "D4") (pin "A") (pinfunction "A_A") (pintype "passive"))
      (node (ref "D5") (pin "A") (pinfunction "A_A") (pintype "passive"))
      (node (ref "U$2") (pin "M2") (pinfunction "1_M2") (pintype "bidirectional"))
    )
    (net (code "56") (name "Net-(U$2M-1)") (class "Default")
      (node (ref "D17") (pin "A") (pinfunction "A_A") (pintype "passive"))
      (node (ref "D20") (pin "A") (pinfunction "A_A") (pintype "passive"))
      (node (ref "U$2") (pin "P2") (pinfunction "1_P2") (pintype "bidirectional"))
    )
    (net (code "57") (name "Net-(U$2N-1)") (class "Default")
      (node (ref "D40") (pin "A") (pinfunction "A_A") (pintype "passive"))
      (node (ref "D43") (pin "A") (pinfunction "A_A") (pintype "passive"))
      (node (ref "U$2") (pin "R2") (pinfunction "1_R2") (pintype "bidirectional"))
    )
    (net (code "58") (name "Net-(U$2O-1)") (class "Default")
      (node (ref "D61") (pin "A") (pinfunction "A_A") (pintype "passive"))
      (node (ref "D63") (pin "A") (pinfunction "A_A") (pintype "passive"))
      (node (ref "U$2") (pin "S2") (pinfunction "1_S2") (pintype "bidirectional"))
    )
  )
)
